# Power-Resistor-Breakout-3W-v001.net
KiCad netlist of a schematic drawn in EAGLE
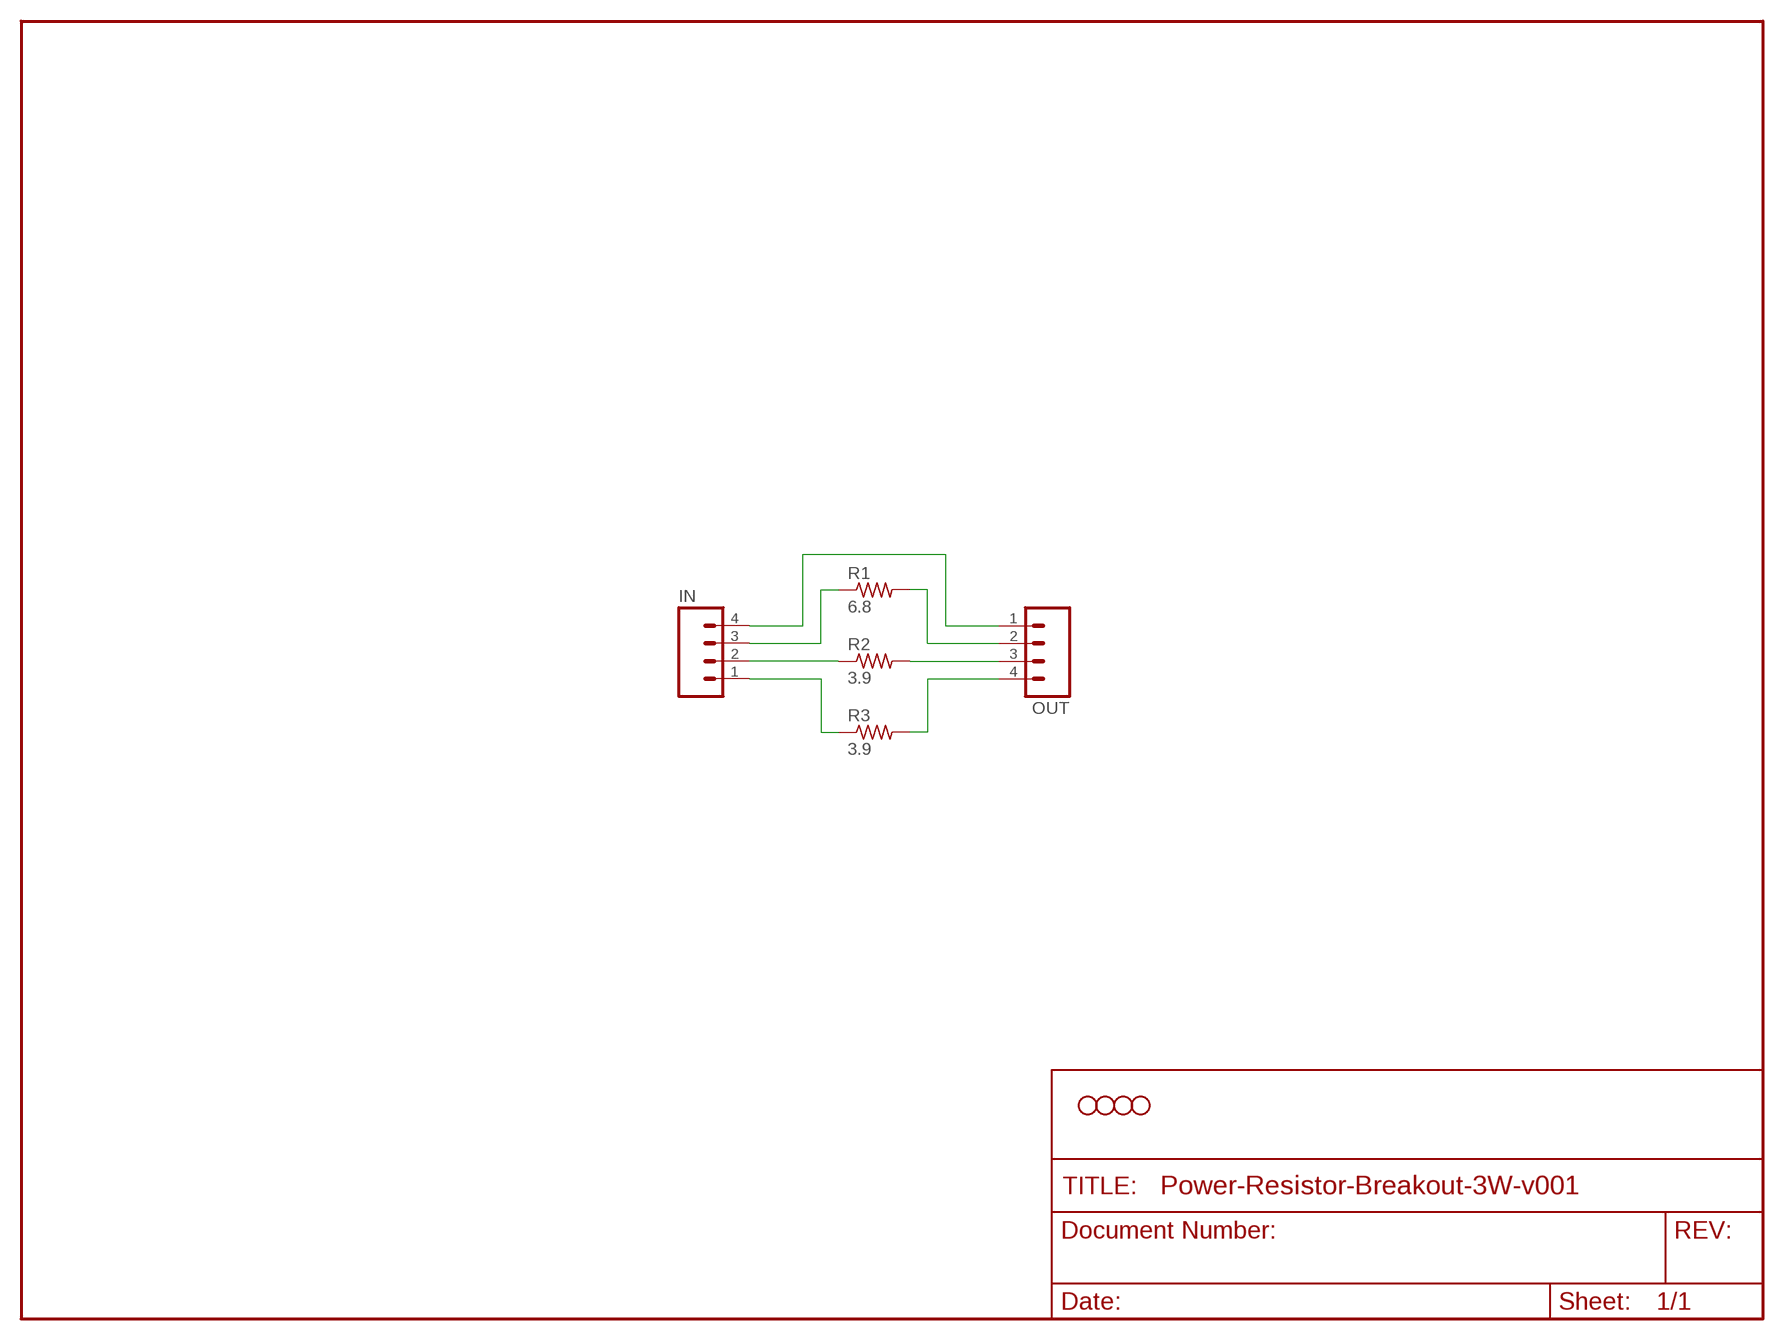
[diagram p0: schematic, sheet 1]

(export (version "E")
  (design (tool "Eeschema 10.0.6"))
  (components
    (comp (ref "IN")
      (value "M04PTH")
      (footprint "eagle-import:1X04")
      (libsource (lib "eagle-import") (part "M04PTH"))
    )
    (comp (ref "JP1")
      (value "STAND-OFF")
      (footprint "eagle-import:STAND-OFF")
      (libsource (lib "eagle-import") (part "STAND-OFF"))
    )
    (comp (ref "JP2")
      (value "STAND-OFF")
      (footprint "eagle-import:STAND-OFF")
      (libsource (lib "eagle-import") (part "STAND-OFF"))
    )
    (comp (ref "JP3")
      (value "STAND-OFF")
      (footprint "eagle-import:STAND-OFF")
      (libsource (lib "eagle-import") (part "STAND-OFF"))
    )
    (comp (ref "JP4")
      (value "STAND-OFF")
      (footprint "eagle-import:STAND-OFF")
      (libsource (lib "eagle-import") (part "STAND-OFF"))
    )
    (comp (ref "OUT")
      (value "M04PTH")
      (footprint "eagle-import:1X04")
      (libsource (lib "eagle-import") (part "M04PTH"))
    )
    (comp (ref "R1")
      (value "6.8")
      (footprint "eagle-import:0411_15")
      (libsource (lib "eagle-import") (part "R-US_0411/15"))
    )
    (comp (ref "R2")
      (value "3.9")
      (footprint "eagle-import:0411_15")
      (libsource (lib "eagle-import") (part "R-US_0411/15"))
    )
    (comp (ref "R3")
      (value "3.9")
      (footprint "eagle-import:0411_15")
      (libsource (lib "eagle-import") (part "R-US_0411/15"))
    )
  )
  (nets
    (net (code "1") (name "Net-(IN-Pad1)") (class "Default")
      (node (ref "IN") (pin "1") (pinfunction "1_1") (pintype "passive"))
      (node (ref "R3") (pin "1") (pinfunction "1_1") (pintype "passive"))
    )
    (net (code "2") (name "Net-(IN-Pad2)") (class "Default")
      (node (ref "IN") (pin "2") (pinfunction "2_2") (pintype "passive"))
      (node (ref "R2") (pin "1") (pinfunction "1_1") (pintype "passive"))
    )
    (net (code "3") (name "Net-(IN-Pad3)") (class "Default")
      (node (ref "IN") (pin "3") (pinfunction "3_3") (pintype "passive"))
      (node (ref "R1") (pin "1") (pinfunction "1_1") (pintype "passive"))
    )
    (net (code "4") (name "Net-(IN-Pad4)") (class "Default")
      (node (ref "IN") (pin "4") (pinfunction "4_4") (pintype "passive"))
      (node (ref "OUT") (pin "1") (pinfunction "1_1") (pintype "passive"))
    )
    (net (code "5") (name "Net-(OUT-Pad2)") (class "Default")
      (node (ref "OUT") (pin "2") (pinfunction "2_2") (pintype "passive"))
      (node (ref "R1") (pin "2") (pinfunction "2_2") (pintype "passive"))
    )
    (net (code "6") (name "Net-(OUT-Pad3)") (class "Default")
      (node (ref "OUT") (pin "3") (pinfunction "3_3") (pintype "passive"))
      (node (ref "R2") (pin "2") (pinfunction "2_2") (pintype "passive"))
    )
    (net (code "7") (name "Net-(OUT-Pad4)") (class "Default")
      (node (ref "OUT") (pin "4") (pinfunction "4_4") (pintype "passive"))
      (node (ref "R3") (pin "2") (pinfunction "2_2") (pintype "passive"))
    )
  )
)
